# SCH_BandBuddy.net
KiCad netlist of a schematic drawn in EasyEDA
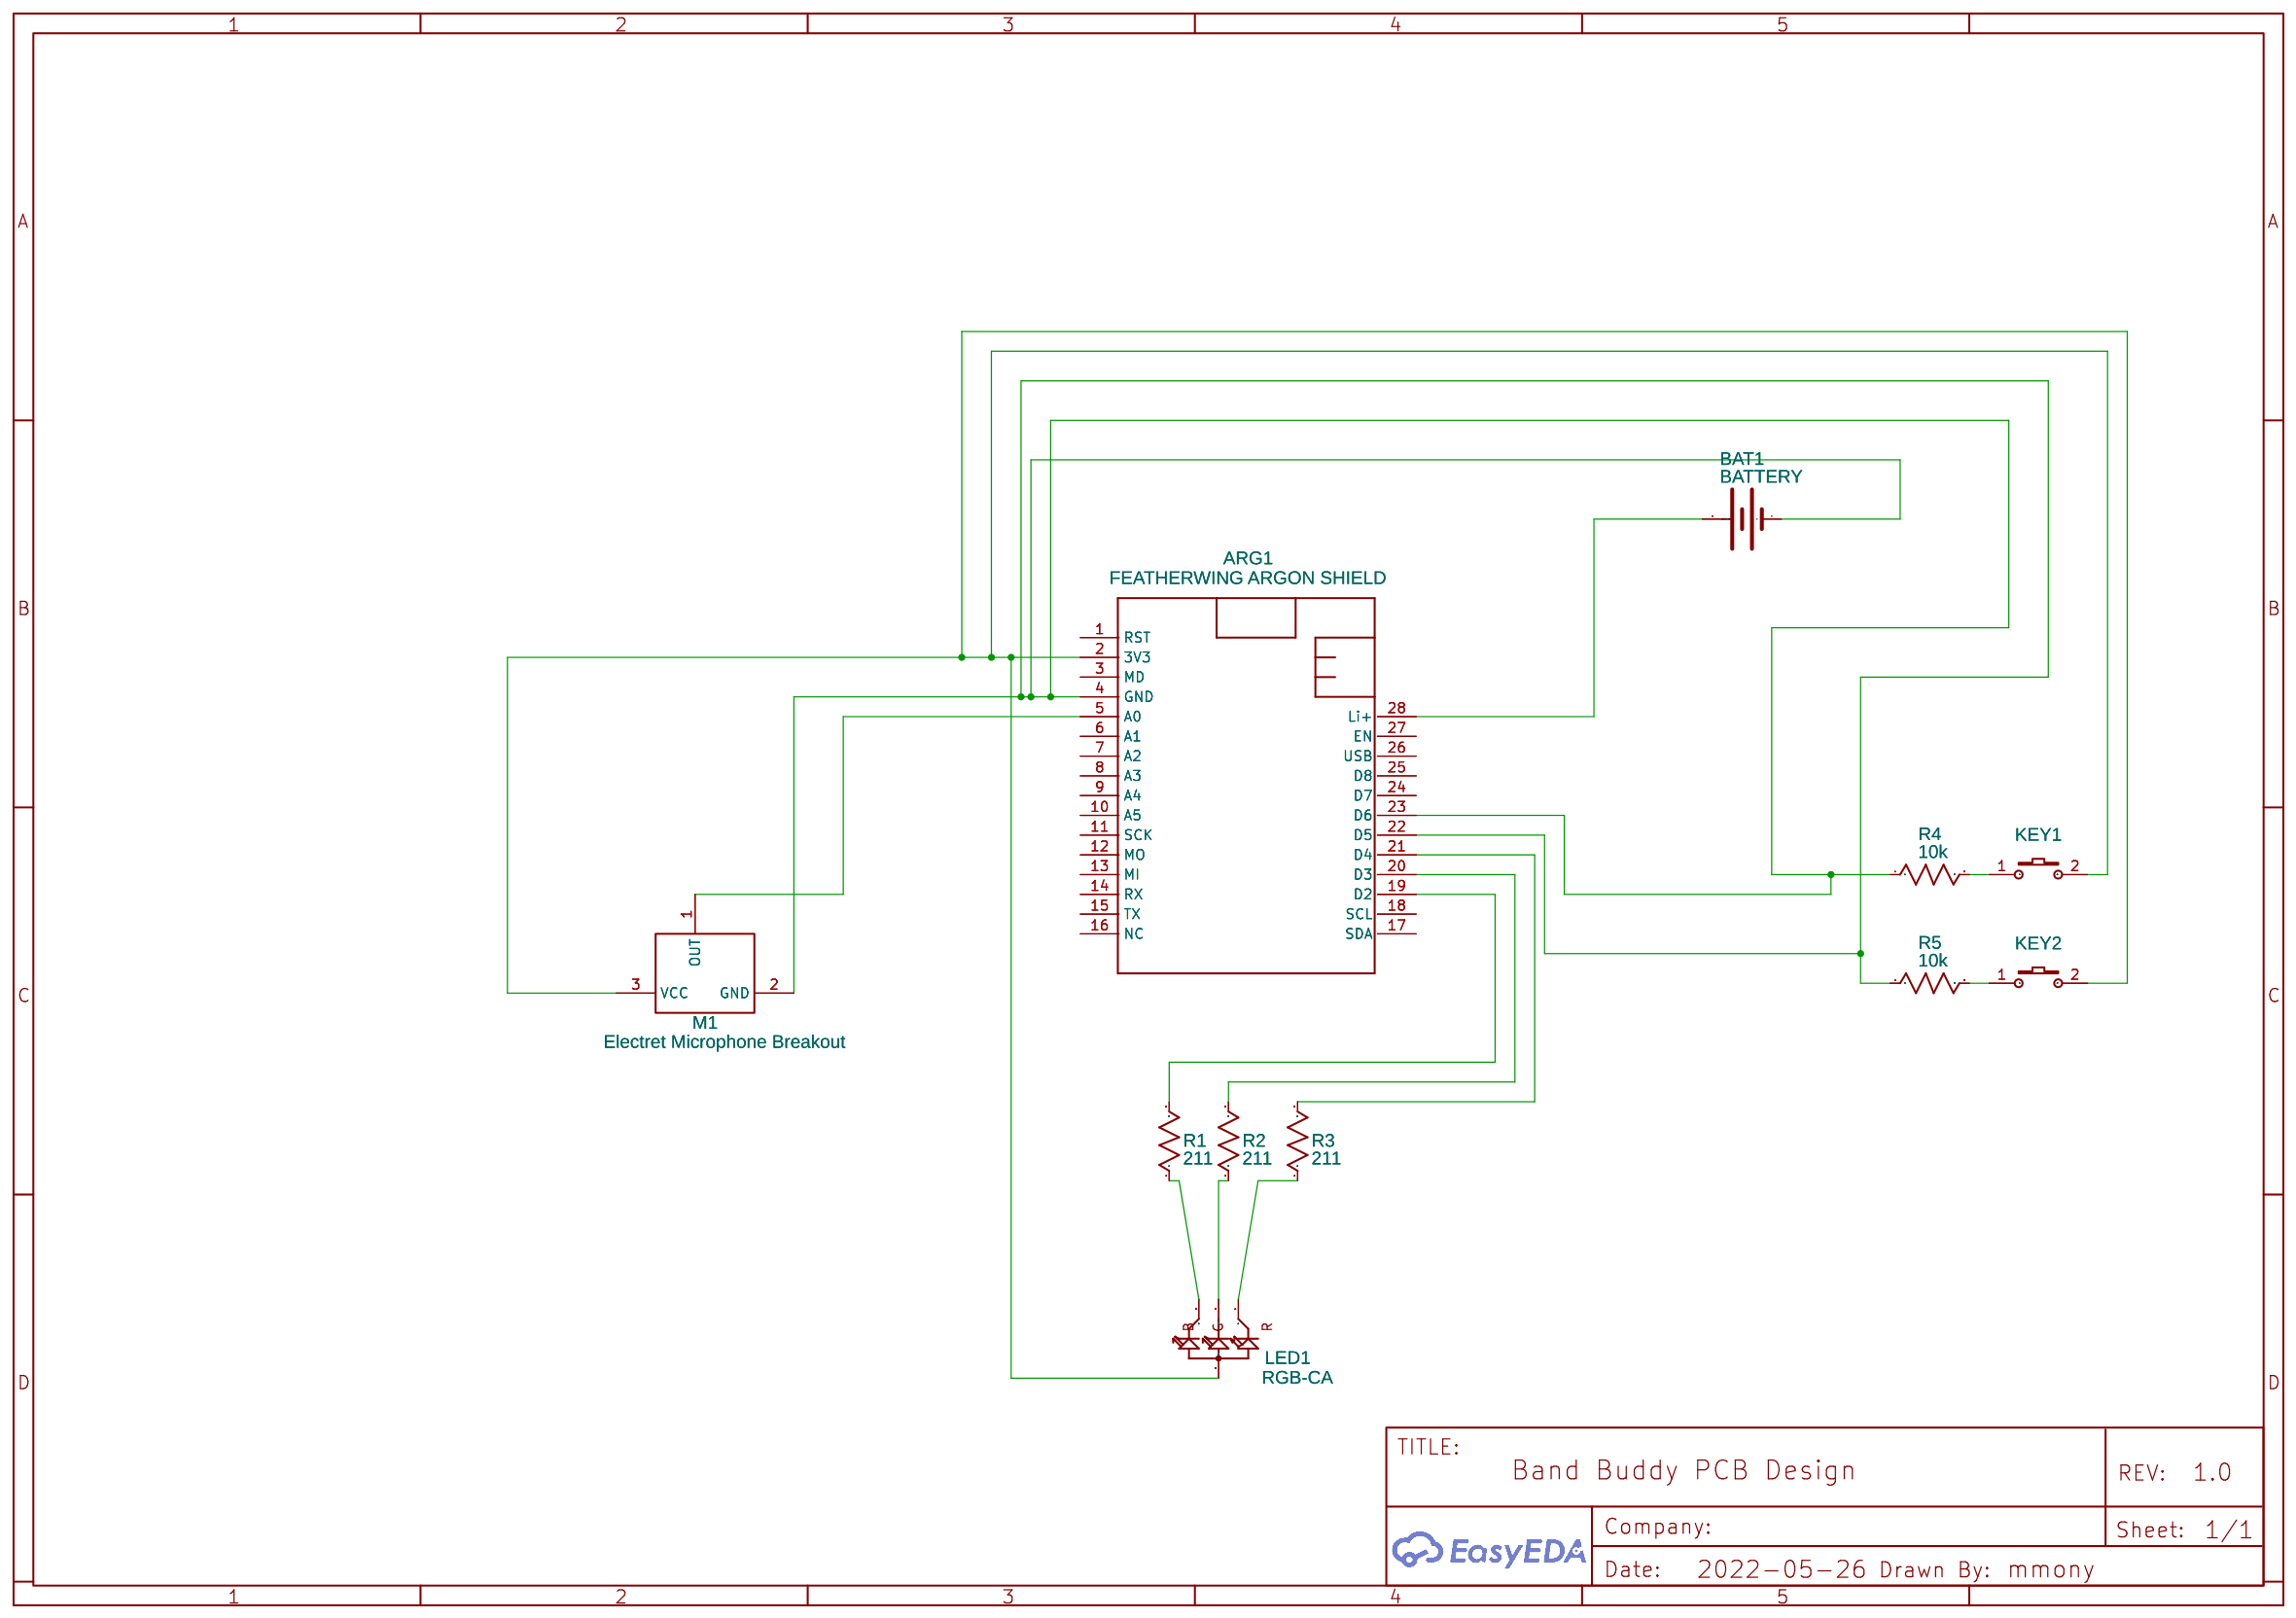
[diagram p0: schematic sheet]

(export (version "E")
  (design (tool "Eeschema 10.0.6"))
  (components
    (comp (ref "ARG1") (value "FEATHERWING ARGON SHIELD") (libsource (lib "") (part "FEATHERWING_NODIM")))
    (comp (ref "BAT1") (value "BATTERY") (libsource (lib "") (part "BATTERY")))
    (comp (ref "KEY1")
      (value "K2-3.6×6.1_SMD")
      (fields
        (field (name "BOM_Manufacturer Part") "K2-1107ST-A4SW-06")
        (field (name "BOM_Supplier Part") "C118141")
      )
      (libsource (lib "") (part "K2-3.6×6.1_SMD"))
    )
    (comp (ref "KEY2")
      (value "K2-3.6×6.1_SMD")
      (fields
        (field (name "BOM_Manufacturer Part") "K2-1107ST-A4SW-06")
        (field (name "BOM_Supplier Part") "C118141")
      )
      (libsource (lib "") (part "K2-3.6×6.1_SMD"))
    )
    (comp (ref "LED1")
      (value "RGB-CA")
      (fields (field (name "BOM_Manufacturer Part") "FZR50RGB00T-C"))
      (libsource (lib "") (part "FZR50RGB00T-C"))
    )
    (comp (ref "M1")
      (value "Electret Microphone Breakout")
      (libsource (lib "") (part "Sound Sensor (Horizontal)"))
    )
    (comp (ref "R1") (value "211") (libsource (lib "") (part "R_0603_US_1")))
    (comp (ref "R2") (value "211") (libsource (lib "") (part "R_0603_US_1")))
    (comp (ref "R3") (value "211") (libsource (lib "") (part "R_0603_US_1")))
    (comp (ref "R4") (value "10k") (libsource (lib "") (part "R_0603_US")))
    (comp (ref "R5") (value "10k") (libsource (lib "") (part "R_0603_US")))
  )
  (nets
    (net (code "1") (name "Net-(ARG1-3V3)") (class "Default")
      (node (ref "ARG1") (pin "2") (pinfunction "3V3_2") (pintype "bidirectional"))
      (node (ref "KEY1") (pin "2") (pinfunction "2_2") (pintype "unspecified"))
      (node (ref "KEY2") (pin "2") (pinfunction "2_2") (pintype "unspecified"))
      (node (ref "LED1") (pin "C") (pinfunction "+_C") (pintype "unspecified"))
      (node (ref "M1") (pin "3") (pinfunction "VCC_3") (pintype "unspecified"))
    )
    (net (code "2") (name "Net-(ARG1-A0)") (class "Default")
      (node (ref "ARG1") (pin "5") (pinfunction "A0_5") (pintype "bidirectional"))
      (node (ref "M1") (pin "1") (pinfunction "OUT_1") (pintype "unspecified"))
    )
    (net (code "3") (name "Net-(ARG1-D2)") (class "Default")
      (node (ref "ARG1") (pin "19") (pinfunction "D2_19") (pintype "bidirectional"))
      (node (ref "R1") (pin "2") (pinfunction "2_2") (pintype "unspecified"))
    )
    (net (code "4") (name "Net-(ARG1-D3)") (class "Default")
      (node (ref "ARG1") (pin "20") (pinfunction "D3_20") (pintype "bidirectional"))
      (node (ref "R2") (pin "2") (pinfunction "2_2") (pintype "unspecified"))
    )
    (net (code "5") (name "Net-(ARG1-D4)") (class "Default")
      (node (ref "ARG1") (pin "21") (pinfunction "D4_21") (pintype "bidirectional"))
      (node (ref "R3") (pin "2") (pinfunction "2_2") (pintype "unspecified"))
    )
    (net (code "6") (name "Net-(ARG1-D5)") (class "Default")
      (node (ref "ARG1") (pin "22") (pinfunction "D5_22") (pintype "bidirectional"))
      (node (ref "ARG1") (pin "23") (pinfunction "D6_23") (pintype "bidirectional"))
      (node (ref "ARG1") (pin "4") (pinfunction "GND_4") (pintype "bidirectional"))
      (node (ref "BAT1") (pin "-") (pinfunction "-_-") (pintype "passive"))
      (node (ref "M1") (pin "2") (pinfunction "GND_2") (pintype "unspecified"))
      (node (ref "R4") (pin "1") (pinfunction "1_1") (pintype "unspecified"))
      (node (ref "R5") (pin "1") (pinfunction "1_1") (pintype "unspecified"))
    )
    (net (code "7") (name "Net-(ARG1-Li+)") (class "Default")
      (node (ref "ARG1") (pin "28") (pinfunction "Li+_28") (pintype "bidirectional"))
      (node (ref "BAT1") (pin "+") (pinfunction "+_+") (pintype "passive"))
    )
    (net (code "8") (name "Net-(KEY1-Pad1)") (class "Default")
      (node (ref "KEY1") (pin "1") (pinfunction "1_1") (pintype "unspecified"))
      (node (ref "R4") (pin "2") (pinfunction "2_2") (pintype "unspecified"))
    )
    (net (code "9") (name "Net-(KEY2-Pad1)") (class "Default")
      (node (ref "KEY2") (pin "1") (pinfunction "1_1") (pintype "unspecified"))
      (node (ref "R5") (pin "2") (pinfunction "2_2") (pintype "unspecified"))
    )
    (net (code "10") (name "Net-(LED1-PadB)") (class "Default")
      (node (ref "LED1") (pin "B") (pinfunction "B_B") (pintype "unspecified"))
      (node (ref "R3") (pin "1") (pinfunction "1_1") (pintype "unspecified"))
    )
    (net (code "11") (name "Net-(LED1-PadG)") (class "Default")
      (node (ref "LED1") (pin "G") (pinfunction "G_G") (pintype "unspecified"))
      (node (ref "R1") (pin "1") (pinfunction "1_1") (pintype "unspecified"))
    )
    (net (code "12") (name "Net-(LED1-PadR)") (class "Default")
      (node (ref "LED1") (pin "R") (pinfunction "R_R") (pintype "unspecified"))
      (node (ref "R2") (pin "1") (pinfunction "1_1") (pintype "unspecified"))
    )
    (net (code "13") (name "unconnected-(ARG1-A1-Pad6)") (class "Default")
      (node (ref "ARG1") (pin "6") (pinfunction "A1_6") (pintype "bidirectional"))
    )
    (net (code "14") (name "unconnected-(ARG1-A2-Pad7)") (class "Default")
      (node (ref "ARG1") (pin "7") (pinfunction "A2_7") (pintype "bidirectional"))
    )
    (net (code "15") (name "unconnected-(ARG1-A3-Pad8)") (class "Default")
      (node (ref "ARG1") (pin "8") (pinfunction "A3_8") (pintype "bidirectional"))
    )
    (net (code "16") (name "unconnected-(ARG1-A4-Pad9)") (class "Default")
      (node (ref "ARG1") (pin "9") (pinfunction "A4_9") (pintype "bidirectional"))
    )
    (net (code "17") (name "unconnected-(ARG1-A5-Pad10)") (class "Default")
      (node (ref "ARG1") (pin "10") (pinfunction "A5_10") (pintype "bidirectional"))
    )
    (net (code "18") (name "unconnected-(ARG1-D7-Pad24)") (class "Default")
      (node (ref "ARG1") (pin "24") (pinfunction "D7_24") (pintype "bidirectional"))
    )
    (net (code "19") (name "unconnected-(ARG1-D8-Pad25)") (class "Default")
      (node (ref "ARG1") (pin "25") (pinfunction "D8_25") (pintype "bidirectional"))
    )
    (net (code "20") (name "unconnected-(ARG1-EN-Pad27)") (class "Default")
      (node (ref "ARG1") (pin "27") (pinfunction "EN_27") (pintype "bidirectional"))
    )
    (net (code "21") (name "unconnected-(ARG1-MD-Pad3)") (class "Default")
      (node (ref "ARG1") (pin "3") (pinfunction "MD_3") (pintype "bidirectional"))
    )
    (net (code "22") (name "unconnected-(ARG1-MI-Pad13)") (class "Default")
      (node (ref "ARG1") (pin "13") (pinfunction "MI_13") (pintype "bidirectional"))
    )
    (net (code "23") (name "unconnected-(ARG1-MO-Pad12)") (class "Default")
      (node (ref "ARG1") (pin "12") (pinfunction "MO_12") (pintype "bidirectional"))
    )
    (net (code "24") (name "unconnected-(ARG1-NC-Pad16)") (class "Default")
      (node (ref "ARG1") (pin "16") (pinfunction "NC_16") (pintype "bidirectional"))
    )
    (net (code "25") (name "unconnected-(ARG1-RST-Pad1)") (class "Default")
      (node (ref "ARG1") (pin "1") (pinfunction "RST_1") (pintype "bidirectional"))
    )
    (net (code "26") (name "unconnected-(ARG1-RX-Pad14)") (class "Default")
      (node (ref "ARG1") (pin "14") (pinfunction "RX_14") (pintype "bidirectional"))
    )
    (net (code "27") (name "unconnected-(ARG1-SCK-Pad11)") (class "Default")
      (node (ref "ARG1") (pin "11") (pinfunction "SCK_11") (pintype "bidirectional"))
    )
    (net (code "28") (name "unconnected-(ARG1-SCL-Pad18)") (class "Default")
      (node (ref "ARG1") (pin "18") (pinfunction "SCL_18") (pintype "bidirectional"))
    )
    (net (code "29") (name "unconnected-(ARG1-SDA-Pad17)") (class "Default")
      (node (ref "ARG1") (pin "17") (pinfunction "SDA_17") (pintype "bidirectional"))
    )
    (net (code "30") (name "unconnected-(ARG1-TX-Pad15)") (class "Default")
      (node (ref "ARG1") (pin "15") (pinfunction "TX_15") (pintype "bidirectional"))
    )
    (net (code "31") (name "unconnected-(ARG1-USB-Pad26)") (class "Default")
      (node (ref "ARG1") (pin "26") (pinfunction "USB_26") (pintype "bidirectional"))
    )
  )
)
